# Table.net
KiCad netlist of a schematic drawn in Altium Designer
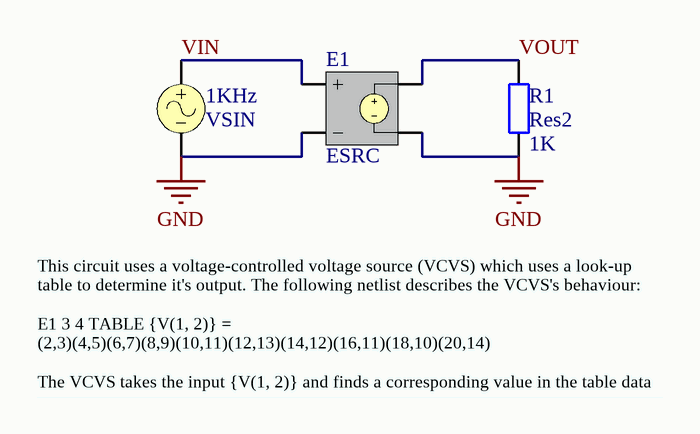
[diagram p0: Table.SCHDOC]

(export (version "E")
  (design (tool "Eeschema 10.0.6"))
  (components
    (comp (ref "1KHz")
      (value "VSIN")
      (description "Sinusoidal Voltage Source")
      (fields (field (name "PUBLISHER") "Altium Limited"))
      (libsource (lib "Simulation Sources") (part "VSIN"))
    )
    (comp (ref "E1")
      (value "ESRC")
      (description "Voltage Controlled Voltage Source")
      (fields (field (name "PUBLISHER") "Altium Limited"))
      (libsource (lib "Simulation Sources") (part "ESRC"))
    )
    (comp (ref "R1")
      (value "Res2")
      (footprint "AXIAL-0.4")
      (description "Resistor")
      (fields (field (name "ALTIUM_VALUE") "1K") (field (name "PUBLISHER") "Altium Limited"))
      (libsource (lib "Miscellaneous Devices") (part "Res2"))
    )
  )
  (nets
    (net (code "1") (name "/VIN") (class "Default")
      (node (ref "1KHz") (pin "1") (pinfunction "1_1") (pintype "passive"))
      (node (ref "E1") (pin "1") (pinfunction "NC+_1") (pintype "passive"))
    )
    (net (code "2") (name "/VOUT") (class "Default")
      (node (ref "E1") (pin "3") (pinfunction "N+_3") (pintype "passive"))
      (node (ref "R1") (pin "2") (pinfunction "2_2") (pintype "passive"))
    )
    (net (code "3") (name "GND") (class "Default")
      (node (ref "1KHz") (pin "2") (pinfunction "2_2") (pintype "passive"))
      (node (ref "E1") (pin "2") (pinfunction "NC-_2") (pintype "passive"))
      (node (ref "E1") (pin "4") (pinfunction "N-_4") (pintype "passive"))
      (node (ref "R1") (pin "1") (pinfunction "1_1") (pintype "passive"))
    )
  )
)
